# BMS_Carrier_-_Current_Sense_Interface.net
KiCad netlist of a schematic drawn in Altium Designer
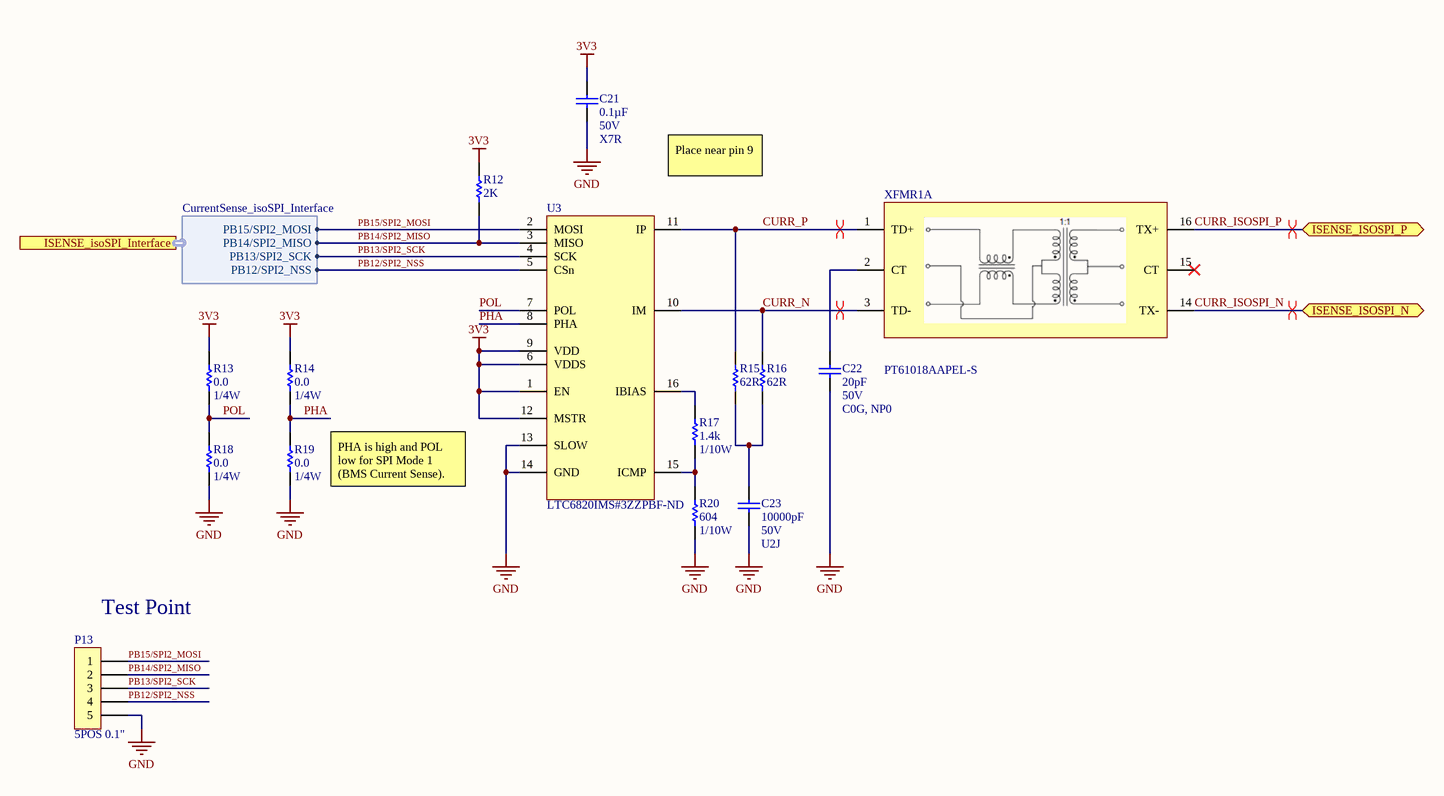
[diagram p0: BMS Carrier - Current Sense Interface.SchDoc]

(export (version "E")
  (design (tool "Eeschema 10.0.6"))
  (components
    (comp (ref "C21")
      (value "CAP CER 0.1UF 50V 10% X7R 0603")
      (footprint "CAP, 0603")
      (description "0.10µF ±10% 50V Ceramic Capacitor X7R 0603 (1608 Metric)")
      (fields
        (field (name "TOLERANCE") "±10%")
        (field (name "CAPACITANCE") "0.1µF")
        (field (name "VOLTAGE") "50V")
        (field (name "TEMPERATURE COEFFICIENT") "X7R")
      )
      (libsource (lib "Schematic Diagrams") (part "CAP CER 0.1UF 50V 10% X7R 0603"))
    )
    (comp (ref "C22")
      (value "CAP CER 20PF 50V ±5% C0G/NP0 0603")
      (footprint "CAP, 0603")
      (description "20pF ±5% 50V Ceramic Capacitor C0G, NP0 0603 (1608 Metric)")
      (fields
        (field (name "TOLERANCE") "±5%")
        (field (name "CAPACITANCE") "20pF")
        (field (name "VOLTAGE") "50V")
        (field (name "TEMPERATURE COEFFICIENT") "C0G, NP0")
      )
      (libsource (lib "Schematic Diagrams") (part "CAP CER 20PF 50V ±5% C0G/NP0 0603"))
    )
    (comp (ref "C23")
      (value "CAP CER 10nF 50V 5% X7R 0603")
      (footprint "CAP, 0603")
      (description "10000pF ±5% 50V Ceramic Capacitor U2J 0603 (1608 Metric)")
      (fields
        (field (name "TOLERANCE") "±5%")
        (field (name "CAPACITANCE") "10000pF")
        (field (name "VOLTAGE") "50V")
        (field (name "TEMPERATURE COEFFICIENT") "U2J")
      )
      (libsource (lib "Schematic Diagrams") (part "CAP CER 10nF 50V 5% X7R 0603"))
    )
    (comp (ref "P13")
      (value "5POS 0.1\"")
      (footprint "CONN, 5POS HEADR 0.1\"")
      (libsource (lib "Schematic Diagrams") (part "CONN 5POS HEADR MALE 0.1{dblquote}"))
    )
    (comp (ref "R12")
      (value "2K")
      (footprint "RES, 0603")
      (description "2k Ohm ±1% 0.1W, 1/10W Chip Resistor 0603 (1608 Metric) Moisture Resistant Thick Film")
      (fields
        (field (name "MANUFACTURER") "Yageo")
        (field (name "MANUFACTURER PART NUMBER") "RC0603FR-072KL")
      )
      (libsource (lib "Schematic Diagrams") (part "RES 2K OHM 1% 1/10W 0603"))
    )
    (comp (ref "R13")
      (value "RES 0.0 OHM 1/4W 0603")
      (footprint "RES, 0603")
      (description "RES SMD 0.0 OHM JUMPER 1/4W 0603")
      (fields (field (name "RESISTANCE") "0.0") (field (name "POWER (WATTS)") "1/4W"))
      (libsource (lib "Schematic Diagrams") (part "RES 0.0 OHM 1/4W 0603"))
    )
    (comp (ref "R14")
      (value "RES 0.0 OHM 1/4W 0603")
      (footprint "RES, 0603")
      (description "RES SMD 0.0 OHM JUMPER 1/4W 0603")
      (fields (field (name "RESISTANCE") "0.0") (field (name "POWER (WATTS)") "1/4W"))
      (libsource (lib "Schematic Diagrams") (part "RES 0.0 OHM 1/4W 0603"))
    )
    (comp (ref "R15")
      (value "62R")
      (footprint "RES, 0603")
      (description "62 Ohms ±0.1% 0.1W, 1/10W Chip Resistor 0603 (1608 Metric) Automotive AEC-Q200 Thin Film")
      (fields
        (field (name "MANUFACTURER") "Panasonic Electronic Components")
        (field (name "MANUFACTURER PART NUMBER") "ERA-3AEB620V")
      )
      (libsource (lib "Schematic Diagrams") (part "RES 62 OHM 0.1% 1/10W 0603"))
    )
    (comp (ref "R16")
      (value "62R")
      (footprint "RES, 0603")
      (description "62 Ohms ±0.1% 0.1W, 1/10W Chip Resistor 0603 (1608 Metric) Automotive AEC-Q200 Thin Film")
      (fields
        (field (name "MANUFACTURER") "Panasonic Electronic Components")
        (field (name "MANUFACTURER PART NUMBER") "ERA-3AEB620V")
      )
      (libsource (lib "Schematic Diagrams") (part "RES 62 OHM 0.1% 1/10W 0603"))
    )
    (comp (ref "R17")
      (value "RES 1.4k OHM 1% 1/10W 0603")
      (footprint "RES, 0603")
      (description "RES SMD 1.4K OHM 1% 1/10W 0603")
      (fields
        (field (name "TOLERANCE") "±1%")
        (field (name "RESISTANCE") "1.4k")
        (field (name "POWER") "1/10W")
      )
      (libsource (lib "Schematic Diagrams") (part "RES 1.4k OHM 1% 1/10W 0603"))
    )
    (comp (ref "R18")
      (value "RES 0.0 OHM 1/4W 0603")
      (footprint "RES, 0603")
      (description "RES SMD 0.0 OHM JUMPER 1/4W 0603")
      (fields (field (name "RESISTANCE") "0.0") (field (name "POWER (WATTS)") "1/4W"))
      (libsource (lib "Schematic Diagrams") (part "RES 0.0 OHM 1/4W 0603"))
    )
    (comp (ref "R19")
      (value "RES 0.0 OHM 1/4W 0603")
      (footprint "RES, 0603")
      (description "RES SMD 0.0 OHM JUMPER 1/4W 0603")
      (fields (field (name "RESISTANCE") "0.0") (field (name "POWER (WATTS)") "1/4W"))
      (libsource (lib "Schematic Diagrams") (part "RES 0.0 OHM 1/4W 0603"))
    )
    (comp (ref "R20")
      (value "RES 604 OHM 1% 1/10W 0603")
      (footprint "RES, 0603")
      (description "RES SMD 604 OHM 1% 1/10W 0603")
      (fields
        (field (name "TOLERANCE") "±1%")
        (field (name "RESISTANCE") "604")
        (field (name "POWER") "1/10W")
      )
      (libsource (lib "Schematic Diagrams") (part "RES 604 OHM 1% 1/10W 0603"))
    )
    (comp (ref "U3")
      (value "IC ISOSPI COMM INTERFACE LTC6820IMS#3ZZPBF")
      (footprint "IC isoSPI Interface LTC6820 MSOP")
      (description "IC COMM INTERFACE ISOSPI 16-MSOP")
      (fields
        (field (name "MANUFACTURER") "Linear Technology")
        (field (name "MANUFACTURER PART NUMBER") "LTC6820IMS#3ZZPBF")
        (field (name "SUPPLIER PART NUMBER 1") "LTC6820IMS#3ZZPBF-ND")
      )
      (libsource (lib "Schematic Diagrams") (part "IC ISOSPI COMM INTERFACE LTC6820IMS#3ZZPBF"))
    )
    (comp (ref "XFMR1")
      (value "IC PULSE XFMR 1CT:1CT 350UH SMD")
      (footprint "IC, PULSE XFMR 1CT:1CT 350UH SMD")
      (description "PULSE XFMR 1CT:1CT 350UH SMD")
      (fields (field (name "MANUFACTURER") "Bourns Inc.") (field (name "MFG_PN") "PT61018AAPEL-S"))
      (libsource (lib "Schematic Diagrams") (part "IC PULSE XFMR 1CT{colon}1CT 350UH SMD"))
    )
  )
  (nets
    (net (code "2") (name "/CURR_ISOSPI_N") (class "Default")
      (node (ref "XFMR1") (pin "14") (pinfunction "TX-_14") (pintype "passive"))
    )
    (net (code "3") (name "/CURR_ISOSPI_P") (class "Default")
      (node (ref "XFMR1") (pin "16") (pinfunction "TX+_16") (pintype "passive"))
    )
    (net (code "4") (name "/CURR_N") (class "Default")
      (node (ref "R16") (pin "1") (pinfunction "1_1") (pintype "passive"))
      (node (ref "U3") (pin "10") (pinfunction "IM_10") (pintype "passive"))
      (node (ref "XFMR1") (pin "3") (pinfunction "TD-_3") (pintype "passive"))
    )
    (net (code "5") (name "/CURR_P") (class "Default")
      (node (ref "R15") (pin "1") (pinfunction "1_1") (pintype "passive"))
      (node (ref "U3") (pin "11") (pinfunction "IP_11") (pintype "passive"))
      (node (ref "XFMR1") (pin "1") (pinfunction "TD+_1") (pintype "passive"))
    )
    (net (code "6") (name "/PB12{slash}SPI2_NSS") (class "Default")
      (node (ref "P13") (pin "4") (pinfunction "4_4") (pintype "passive"))
      (node (ref "U3") (pin "5") (pinfunction "CSn_5") (pintype "passive"))
    )
    (net (code "7") (name "/PB13{slash}SPI2_SCK") (class "Default")
      (node (ref "P13") (pin "3") (pinfunction "3_3") (pintype "passive"))
      (node (ref "U3") (pin "4") (pinfunction "SCK_4") (pintype "passive"))
    )
    (net (code "8") (name "/PB14{slash}SPI2_MISO") (class "Default")
      (node (ref "P13") (pin "2") (pinfunction "2_2") (pintype "passive"))
      (node (ref "R12") (pin "2") (pinfunction "2_2") (pintype "passive"))
      (node (ref "U3") (pin "3") (pinfunction "MISO_3") (pintype "passive"))
    )
    (net (code "9") (name "/PB15{slash}SPI2_MOSI") (class "Default")
      (node (ref "P13") (pin "1") (pinfunction "1_1") (pintype "passive"))
      (node (ref "U3") (pin "2") (pinfunction "MOSI_2") (pintype "passive"))
    )
    (net (code "10") (name "/PHA") (class "Default")
      (node (ref "R14") (pin "2") (pinfunction "2_2") (pintype "passive"))
      (node (ref "R19") (pin "1") (pinfunction "1_1") (pintype "passive"))
      (node (ref "U3") (pin "8") (pinfunction "PHA_8") (pintype "passive"))
    )
    (net (code "11") (name "/POL") (class "Default")
      (node (ref "R13") (pin "2") (pinfunction "2_2") (pintype "passive"))
      (node (ref "R18") (pin "1") (pinfunction "1_1") (pintype "passive"))
      (node (ref "U3") (pin "7") (pinfunction "POL_7") (pintype "passive"))
    )
    (net (code "13") (name "3V3") (class "Default")
      (node (ref "C21") (pin "1") (pinfunction "1_1") (pintype "passive"))
      (node (ref "R12") (pin "1") (pinfunction "1_1") (pintype "passive"))
      (node (ref "R13") (pin "1") (pinfunction "1_1") (pintype "passive"))
      (node (ref "R14") (pin "1") (pinfunction "1_1") (pintype "passive"))
      (node (ref "U3") (pin "1") (pinfunction "EN_1") (pintype "passive"))
      (node (ref "U3") (pin "12") (pinfunction "MSTR_12") (pintype "passive"))
      (node (ref "U3") (pin "6") (pinfunction "VDDS_6") (pintype "passive"))
      (node (ref "U3") (pin "9") (pinfunction "VDD_9") (pintype "passive"))
    )
    (net (code "14") (name "GND") (class "Default")
      (node (ref "C21") (pin "2") (pinfunction "2_2") (pintype "passive"))
      (node (ref "C22") (pin "2") (pinfunction "2_2") (pintype "passive"))
      (node (ref "C23") (pin "2") (pinfunction "2_2") (pintype "passive"))
      (node (ref "P13") (pin "5") (pinfunction "5_5") (pintype "passive"))
      (node (ref "R18") (pin "2") (pinfunction "2_2") (pintype "passive"))
      (node (ref "R19") (pin "2") (pinfunction "2_2") (pintype "passive"))
      (node (ref "R20") (pin "2") (pinfunction "2_2") (pintype "passive"))
      (node (ref "U3") (pin "13") (pinfunction "SLOW_13") (pintype "passive"))
      (node (ref "U3") (pin "14") (pinfunction "GND_14") (pintype "passive"))
    )
    (net (code "15") (name "Net-(C22-Pad1)") (class "Default")
      (node (ref "C22") (pin "1") (pinfunction "1_1") (pintype "passive"))
      (node (ref "XFMR1") (pin "2") (pinfunction "CT_2") (pintype "passive"))
    )
    (net (code "16") (name "Net-(C23-Pad1)") (class "Default")
      (node (ref "C23") (pin "1") (pinfunction "1_1") (pintype "passive"))
      (node (ref "R15") (pin "2") (pinfunction "2_2") (pintype "passive"))
      (node (ref "R16") (pin "2") (pinfunction "2_2") (pintype "passive"))
    )
    (net (code "17") (name "Net-(U3-IBIAS)") (class "Default")
      (node (ref "R17") (pin "1") (pinfunction "1_1") (pintype "passive"))
      (node (ref "U3") (pin "16") (pinfunction "IBIAS_16") (pintype "passive"))
    )
    (net (code "18") (name "Net-(U3-ICMP)") (class "Default")
      (node (ref "R17") (pin "2") (pinfunction "2_2") (pintype "passive"))
      (node (ref "R20") (pin "1") (pinfunction "1_1") (pintype "passive"))
      (node (ref "U3") (pin "15") (pinfunction "ICMP_15") (pintype "passive"))
    )
    (net (code "19") (name "unconnected-(XFMR1A-CT-Pad15)") (class "Default")
      (node (ref "XFMR1") (pin "15") (pinfunction "CT_15") (pintype "passive+no_connect"))
    )
  )
)
